# ROB.net
KiCad netlist of a schematic drawn in EAGLE
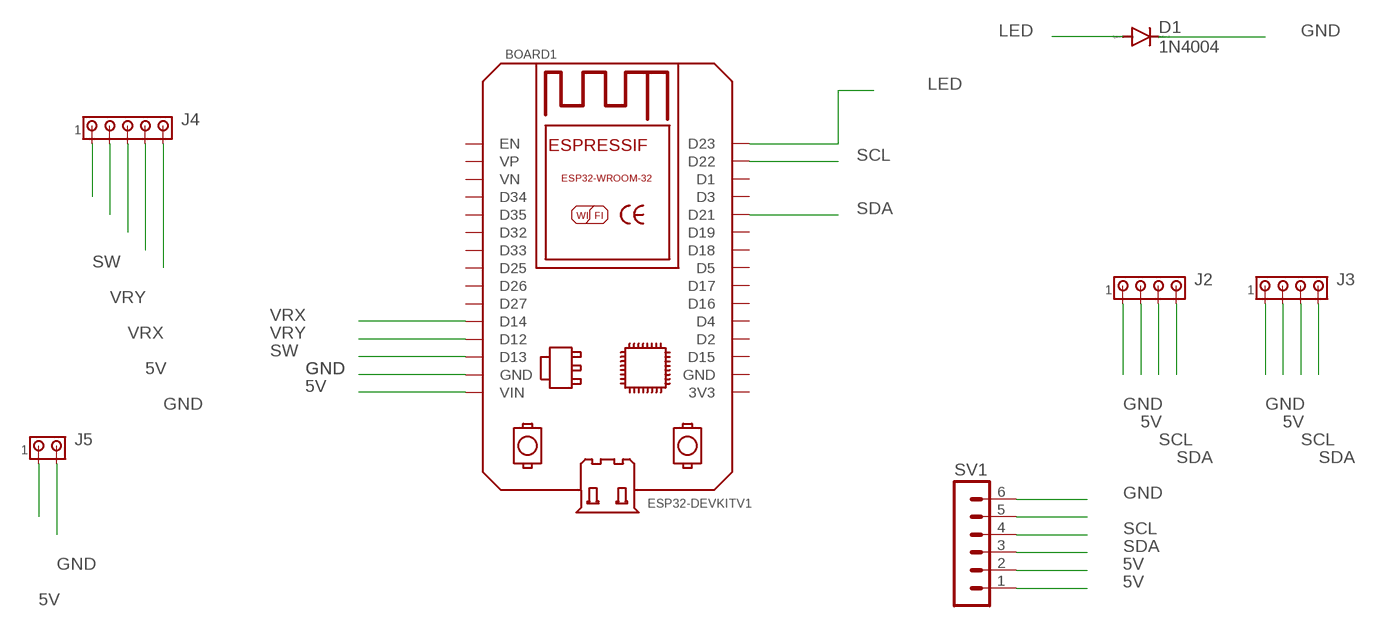
[diagram p0: schematic, sheet 1]

(export (version "E")
  (design (tool "Eeschema 10.0.6"))
  (components
    (comp (ref "BOARD1")
      (value "ESP32DEVKITV1")
      (footprint "eagle-import:ESP32-DEVKITV1")
      (libsource (lib "eagle-import") (part "ESP32DEVKITV1"))
    )
    (comp (ref "D1")
      (value "1N4004")
      (footprint "eagle-import:DO41-10")
      (libsource (lib "eagle-import") (part "1N4004"))
    )
    (comp (ref "J2")
      (value "MTA04-100")
      (footprint "eagle-import:10X04MTA")
      (libsource (lib "eagle-import") (part "MTA04-100"))
    )
    (comp (ref "J3")
      (value "MTA04-100")
      (footprint "eagle-import:10X04MTA")
      (libsource (lib "eagle-import") (part "MTA04-100"))
    )
    (comp (ref "J4")
      (value "MTA05-100")
      (footprint "eagle-import:10X05MTA")
      (libsource (lib "eagle-import") (part "MTA05-100"))
    )
    (comp (ref "J5")
      (value "MTA02-156")
      (footprint "eagle-import:1X2MTA")
      (libsource (lib "eagle-import") (part "MTA02-156"))
    )
    (comp (ref "SV1")
      (value "MA06-1")
      (footprint "eagle-import:MA06-1")
      (libsource (lib "eagle-import") (part "MA06-1"))
    )
  )
  (nets
    (net (code "1") (name "/5V") (class "Default")
      (node (ref "BOARD1") (pin "VIN") (pinfunction "VIN_VIN") (pintype "bidirectional"))
      (node (ref "J2") (pin "2") (pinfunction "2_2") (pintype "passive"))
      (node (ref "J3") (pin "2") (pinfunction "2_2") (pintype "passive"))
      (node (ref "J4") (pin "4") (pinfunction "4_4") (pintype "passive"))
      (node (ref "J5") (pin "1") (pinfunction "1_1") (pintype "passive"))
      (node (ref "SV1") (pin "1") (pinfunction "1_1") (pintype "passive"))
      (node (ref "SV1") (pin "2") (pinfunction "2_2") (pintype "passive"))
    )
    (net (code "2") (name "/GND") (class "Default")
      (node (ref "BOARD1") (pin "GND") (pinfunction "GND_GND") (pintype "bidirectional"))
      (node (ref "D1") (pin "C") (pinfunction "C_C") (pintype "passive"))
      (node (ref "J2") (pin "1") (pinfunction "1_1") (pintype "passive"))
      (node (ref "J3") (pin "1") (pinfunction "1_1") (pintype "passive"))
      (node (ref "J4") (pin "5") (pinfunction "5_5") (pintype "passive"))
      (node (ref "J5") (pin "2") (pinfunction "2_2") (pintype "passive"))
      (node (ref "SV1") (pin "6") (pinfunction "6_6") (pintype "passive"))
    )
    (net (code "3") (name "/LED") (class "Default")
      (node (ref "BOARD1") (pin "D23") (pinfunction "D23_D23") (pintype "bidirectional"))
      (node (ref "D1") (pin "A") (pinfunction "A_A") (pintype "passive"))
    )
    (net (code "4") (name "/SCL") (class "Default")
      (node (ref "BOARD1") (pin "D22") (pinfunction "D22_D22") (pintype "bidirectional"))
      (node (ref "J2") (pin "3") (pinfunction "3_3") (pintype "passive"))
      (node (ref "J3") (pin "3") (pinfunction "3_3") (pintype "passive"))
      (node (ref "SV1") (pin "4") (pinfunction "4_4") (pintype "passive"))
    )
    (net (code "5") (name "/SDA") (class "Default")
      (node (ref "BOARD1") (pin "D21") (pinfunction "D21_D21") (pintype "bidirectional"))
      (node (ref "J2") (pin "4") (pinfunction "4_4") (pintype "passive"))
      (node (ref "J3") (pin "4") (pinfunction "4_4") (pintype "passive"))
      (node (ref "SV1") (pin "3") (pinfunction "3_3") (pintype "passive"))
    )
    (net (code "6") (name "/SW") (class "Default")
      (node (ref "BOARD1") (pin "D13") (pinfunction "D13_D13") (pintype "bidirectional"))
      (node (ref "J4") (pin "1") (pinfunction "1_1") (pintype "passive"))
    )
    (net (code "7") (name "/VRX") (class "Default")
      (node (ref "BOARD1") (pin "D14") (pinfunction "D14_D14") (pintype "bidirectional"))
      (node (ref "J4") (pin "3") (pinfunction "3_3") (pintype "passive"))
    )
    (net (code "8") (name "/VRY") (class "Default")
      (node (ref "BOARD1") (pin "D12") (pinfunction "D12_D12") (pintype "bidirectional"))
      (node (ref "J4") (pin "2") (pinfunction "2_2") (pintype "passive"))
    )
    (net (code "9") (name "unconnected-(BOARD1-GND-PadGND@1)") (class "Default")
      (node (ref "BOARD1") (pin "GND@1") (pinfunction "GND_GND@1") (pintype "bidirectional"))
    )
    (net (code "10") (name "unconnected-(BOARD1-Pad3V3)") (class "Default")
      (node (ref "BOARD1") (pin "3V3") (pinfunction "3V3_3V3") (pintype "bidirectional"))
    )
    (net (code "11") (name "unconnected-(BOARD1-PadD1)") (class "Default")
      (node (ref "BOARD1") (pin "D1") (pinfunction "D1_D1") (pintype "bidirectional"))
    )
    (net (code "12") (name "unconnected-(BOARD1-PadD2)") (class "Default")
      (node (ref "BOARD1") (pin "D2") (pinfunction "D2_D2") (pintype "bidirectional"))
    )
    (net (code "13") (name "unconnected-(BOARD1-PadD3)") (class "Default")
      (node (ref "BOARD1") (pin "D3") (pinfunction "D3_D3") (pintype "bidirectional"))
    )
    (net (code "14") (name "unconnected-(BOARD1-PadD4)") (class "Default")
      (node (ref "BOARD1") (pin "D4") (pinfunction "D4_D4") (pintype "bidirectional"))
    )
    (net (code "15") (name "unconnected-(BOARD1-PadD5)") (class "Default")
      (node (ref "BOARD1") (pin "D5") (pinfunction "D5_D5") (pintype "bidirectional"))
    )
    (net (code "16") (name "unconnected-(BOARD1-PadD15)") (class "Default")
      (node (ref "BOARD1") (pin "D15") (pinfunction "D15_D15") (pintype "bidirectional"))
    )
    (net (code "17") (name "unconnected-(BOARD1-PadD16)") (class "Default")
      (node (ref "BOARD1") (pin "D16") (pinfunction "D16_D16") (pintype "bidirectional"))
    )
    (net (code "18") (name "unconnected-(BOARD1-PadD17)") (class "Default")
      (node (ref "BOARD1") (pin "D17") (pinfunction "D17_D17") (pintype "bidirectional"))
    )
    (net (code "19") (name "unconnected-(BOARD1-PadD18)") (class "Default")
      (node (ref "BOARD1") (pin "D18") (pinfunction "D18_D18") (pintype "bidirectional"))
    )
    (net (code "20") (name "unconnected-(BOARD1-PadD19)") (class "Default")
      (node (ref "BOARD1") (pin "D19") (pinfunction "D19_D19") (pintype "bidirectional"))
    )
    (net (code "21") (name "unconnected-(BOARD1-PadD25)") (class "Default")
      (node (ref "BOARD1") (pin "D25") (pinfunction "D25_D25") (pintype "bidirectional"))
    )
    (net (code "22") (name "unconnected-(BOARD1-PadD26)") (class "Default")
      (node (ref "BOARD1") (pin "D26") (pinfunction "D26_D26") (pintype "bidirectional"))
    )
    (net (code "23") (name "unconnected-(BOARD1-PadD27)") (class "Default")
      (node (ref "BOARD1") (pin "D27") (pinfunction "D27_D27") (pintype "bidirectional"))
    )
    (net (code "24") (name "unconnected-(BOARD1-PadD32)") (class "Default")
      (node (ref "BOARD1") (pin "D32") (pinfunction "D32_D32") (pintype "bidirectional"))
    )
    (net (code "25") (name "unconnected-(BOARD1-PadD33)") (class "Default")
      (node (ref "BOARD1") (pin "D33") (pinfunction "D33_D33") (pintype "bidirectional"))
    )
    (net (code "26") (name "unconnected-(BOARD1-PadD34)") (class "Default")
      (node (ref "BOARD1") (pin "D34") (pinfunction "D34_D34") (pintype "bidirectional"))
    )
    (net (code "27") (name "unconnected-(BOARD1-PadD35)") (class "Default")
      (node (ref "BOARD1") (pin "D35") (pinfunction "D35_D35") (pintype "bidirectional"))
    )
    (net (code "28") (name "unconnected-(BOARD1-PadEN)") (class "Default")
      (node (ref "BOARD1") (pin "EN") (pinfunction "EN_EN") (pintype "bidirectional"))
    )
    (net (code "29") (name "unconnected-(BOARD1-PadVN)") (class "Default")
      (node (ref "BOARD1") (pin "VN") (pinfunction "VN_VN") (pintype "bidirectional"))
    )
    (net (code "30") (name "unconnected-(BOARD1-PadVP)") (class "Default")
      (node (ref "BOARD1") (pin "VP") (pinfunction "VP_VP") (pintype "bidirectional"))
    )
    (net (code "31") (name "unconnected-(SV1-Pad5)") (class "Default")
      (node (ref "SV1") (pin "5") (pinfunction "5_5") (pintype "passive"))
    )
  )
)
